# business_card_serial_uv.net
KiCad netlist of a schematic drawn in EAGLE
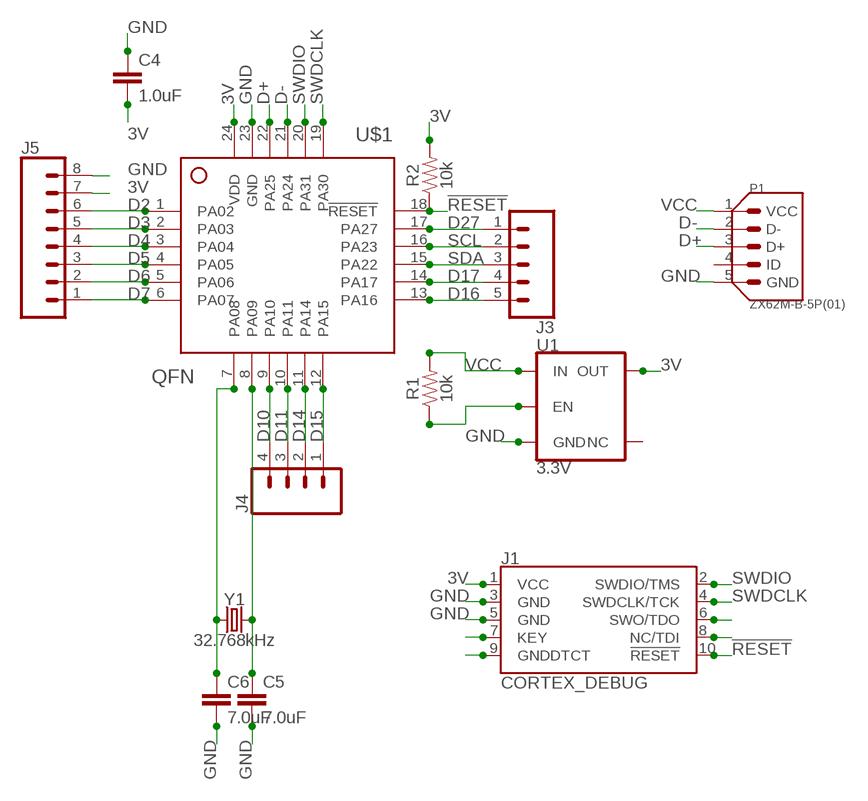
[diagram p0: schematic, sheet 1]

(export (version "E")
  (design (tool "Eeschema 10.0.6"))
  (components
    (comp (ref "C4")
      (value "1.0uF")
      (footprint "eagle-import:0402")
      (libsource (lib "eagle-import") (part "1.0UF-0402-16V-10%"))
    )
    (comp (ref "C5")
      (value "7.0uF")
      (footprint "eagle-import:0402")
      (libsource (lib "eagle-import") (part "1.0UF-0402-16V-10%"))
    )
    (comp (ref "C6")
      (value "7.0uF")
      (footprint "eagle-import:0402")
      (libsource (lib "eagle-import") (part "1.0UF-0402-16V-10%"))
    )
    (comp (ref "J1")
      (value "CORTEX_DEBUG")
      (footprint "eagle-import:2X5-PTH-1.27MM")
      (libsource (lib "eagle-import") (part "CORTEX_DEBUG_PTH"))
    )
    (comp (ref "J3")
      (value "CONN_05")
      (footprint "eagle-import:1X05")
      (libsource (lib "eagle-import") (part "CONN_05"))
    )
    (comp (ref "J4")
      (value "CONN_04")
      (footprint "eagle-import:1X04")
      (libsource (lib "eagle-import") (part "CONN_04"))
    )
    (comp (ref "J5")
      (value "CONN_08\"")
      (footprint "eagle-import:1X08")
      (libsource (lib "eagle-import") (part "CONN_08{dblquote}"))
    )
    (comp (ref "P1")
      (value "ZX62M-B-5P(01)")
      (footprint "eagle-import:HRS_ZX62M-B-5P(01)")
      (fields (field (name "MF") "Hirose") (field (name "MP") "ZX62M-B-5P_01_"))
      (libsource (lib "eagle-import") (part "ZX62M-B-5P(01)"))
    )
    (comp (ref "R1")
      (value "10k")
      (footprint "eagle-import:0603")
      (libsource (lib "eagle-import") (part "330OHM-0603-1/10W-1%"))
    )
    (comp (ref "R2")
      (value "10k")
      (footprint "eagle-import:0603")
      (libsource (lib "eagle-import") (part "330OHM-0603-1/10W-1%"))
    )
    (comp (ref "U$1")
      (value "QFN")
      (footprint "eagle-import:QFN24-4X4")
      (libsource (lib "eagle-import") (part "QFN"))
    )
    (comp (ref "U1")
      (value "3.3V")
      (footprint "eagle-import:SOT23-5")
      (libsource (lib "eagle-import") (part "V_REG_AP2112K-3.3V"))
    )
    (comp (ref "Y1")
      (value "32.768kHz")
      (footprint "eagle-import:CRYSTAL-SMD-3.2X1.5MM")
      (libsource (lib "eagle-import") (part "CRYSTAL-32.768KHZSMD-3.2X1.5"))
    )
  )
  (nets
    (net (code "1") (name "/3V") (class "Default")
      (node (ref "C4") (pin "2") (pinfunction "2_2") (pintype "passive"))
      (node (ref "J1") (pin "1") (pinfunction "VCC_1") (pintype "bidirectional"))
      (node (ref "J5") (pin "7") (pinfunction "7_7") (pintype "passive"))
      (node (ref "R2") (pin "2") (pinfunction "2_2") (pintype "passive"))
      (node (ref "U$1") (pin "24") (pinfunction "VDD_24") (pintype "bidirectional"))
      (node (ref "U1") (pin "5") (pinfunction "OUT_5") (pintype "passive"))
    )
    (net (code "2") (name "/D+") (class "Default")
      (node (ref "P1") (pin "3") (pinfunction "D+_3") (pintype "bidirectional"))
      (node (ref "U$1") (pin "22") (pinfunction "PA25_22") (pintype "bidirectional"))
    )
    (net (code "3") (name "/D-") (class "Default")
      (node (ref "P1") (pin "2") (pinfunction "D-_2") (pintype "bidirectional"))
      (node (ref "U$1") (pin "21") (pinfunction "PA24_21") (pintype "bidirectional"))
    )
    (net (code "4") (name "/D2") (class "Default")
      (node (ref "J5") (pin "6") (pinfunction "6_6") (pintype "passive"))
      (node (ref "U$1") (pin "1") (pinfunction "PA02_1") (pintype "bidirectional"))
    )
    (net (code "5") (name "/D3") (class "Default")
      (node (ref "J5") (pin "5") (pinfunction "5_5") (pintype "passive"))
      (node (ref "U$1") (pin "2") (pinfunction "PA03_2") (pintype "bidirectional"))
    )
    (net (code "6") (name "/D4") (class "Default")
      (node (ref "J5") (pin "4") (pinfunction "4_4") (pintype "passive"))
      (node (ref "U$1") (pin "3") (pinfunction "PA04_3") (pintype "bidirectional"))
    )
    (net (code "7") (name "/D5") (class "Default")
      (node (ref "J5") (pin "3") (pinfunction "3_3") (pintype "passive"))
      (node (ref "U$1") (pin "4") (pinfunction "PA05_4") (pintype "bidirectional"))
    )
    (net (code "8") (name "/D6") (class "Default")
      (node (ref "J5") (pin "2") (pinfunction "2_2") (pintype "passive"))
      (node (ref "U$1") (pin "5") (pinfunction "PA06_5") (pintype "bidirectional"))
    )
    (net (code "9") (name "/D7") (class "Default")
      (node (ref "J5") (pin "1") (pinfunction "1_1") (pintype "passive"))
      (node (ref "U$1") (pin "6") (pinfunction "PA07_6") (pintype "bidirectional"))
    )
    (net (code "10") (name "/D10") (class "Default")
      (node (ref "J4") (pin "4") (pinfunction "4_4") (pintype "passive"))
      (node (ref "U$1") (pin "9") (pinfunction "PA10_9") (pintype "bidirectional"))
    )
    (net (code "11") (name "/D11") (class "Default")
      (node (ref "J4") (pin "3") (pinfunction "3_3") (pintype "passive"))
      (node (ref "U$1") (pin "10") (pinfunction "PA11_10") (pintype "bidirectional"))
    )
    (net (code "12") (name "/D14") (class "Default")
      (node (ref "J4") (pin "2") (pinfunction "2_2") (pintype "passive"))
      (node (ref "U$1") (pin "11") (pinfunction "PA14_11") (pintype "bidirectional"))
    )
    (net (code "13") (name "/D15") (class "Default")
      (node (ref "J4") (pin "1") (pinfunction "1_1") (pintype "passive"))
      (node (ref "U$1") (pin "12") (pinfunction "PA15_12") (pintype "bidirectional"))
    )
    (net (code "14") (name "/D16") (class "Default")
      (node (ref "J3") (pin "5") (pinfunction "5_5") (pintype "passive"))
      (node (ref "U$1") (pin "13") (pinfunction "PA16_13") (pintype "bidirectional"))
    )
    (net (code "15") (name "/D17") (class "Default")
      (node (ref "J3") (pin "4") (pinfunction "4_4") (pintype "passive"))
      (node (ref "U$1") (pin "14") (pinfunction "PA17_14") (pintype "bidirectional"))
    )
    (net (code "16") (name "/D27") (class "Default")
      (node (ref "J3") (pin "1") (pinfunction "1_1") (pintype "passive"))
      (node (ref "U$1") (pin "17") (pinfunction "PA27_17") (pintype "bidirectional"))
    )
    (net (code "17") (name "/GND") (class "Default")
      (node (ref "C4") (pin "1") (pinfunction "1_1") (pintype "passive"))
      (node (ref "C5") (pin "2") (pinfunction "2_2") (pintype "passive"))
      (node (ref "C6") (pin "2") (pinfunction "2_2") (pintype "passive"))
      (node (ref "J1") (pin "3") (pinfunction "GND_3") (pintype "bidirectional"))
      (node (ref "J1") (pin "5") (pinfunction "GND_5") (pintype "bidirectional"))
      (node (ref "J5") (pin "8") (pinfunction "8_8") (pintype "passive"))
      (node (ref "P1") (pin "5") (pinfunction "GND_5") (pintype "passive"))
      (node (ref "U$1") (pin "23") (pinfunction "GND_23") (pintype "bidirectional"))
      (node (ref "U1") (pin "2") (pinfunction "GND_2") (pintype "input"))
    )
    (net (code "18") (name "/SCL") (class "Default")
      (node (ref "J3") (pin "2") (pinfunction "2_2") (pintype "passive"))
      (node (ref "U$1") (pin "16") (pinfunction "PA23_16") (pintype "bidirectional"))
    )
    (net (code "19") (name "/SDA") (class "Default")
      (node (ref "J3") (pin "3") (pinfunction "3_3") (pintype "passive"))
      (node (ref "U$1") (pin "15") (pinfunction "PA22_15") (pintype "bidirectional"))
    )
    (net (code "20") (name "/SWDCLK") (class "Default")
      (node (ref "J1") (pin "4") (pinfunction "SWDCLK/TCK_4") (pintype "bidirectional"))
      (node (ref "U$1") (pin "19") (pinfunction "PA30_19") (pintype "bidirectional"))
    )
    (net (code "21") (name "/SWDIO") (class "Default")
      (node (ref "J1") (pin "2") (pinfunction "SWDIO/TMS_2") (pintype "bidirectional"))
      (node (ref "U$1") (pin "20") (pinfunction "PA31_20") (pintype "bidirectional"))
    )
    (net (code "22") (name "/VCC") (class "Default")
      (node (ref "P1") (pin "1") (pinfunction "VCC_1") (pintype "power_in"))
      (node (ref "R1") (pin "2") (pinfunction "2_2") (pintype "passive"))
      (node (ref "U1") (pin "1") (pinfunction "IN_1") (pintype "input"))
    )
    (net (code "23") (name "/~{RESET}") (class "Default")
      (node (ref "J1") (pin "10") (pinfunction "~{RESET}_10") (pintype "bidirectional"))
      (node (ref "R2") (pin "1") (pinfunction "1_1") (pintype "passive"))
      (node (ref "U$1") (pin "18") (pinfunction "~{RESET}_18") (pintype "bidirectional"))
    )
    (net (code "24") (name "Net-(U$1-PA08)") (class "Default")
      (node (ref "C6") (pin "1") (pinfunction "1_1") (pintype "passive"))
      (node (ref "U$1") (pin "7") (pinfunction "PA08_7") (pintype "bidirectional"))
      (node (ref "Y1") (pin "P$1") (pinfunction "1_P$1") (pintype "passive"))
    )
    (net (code "25") (name "Net-(U$1-PA09)") (class "Default")
      (node (ref "C5") (pin "1") (pinfunction "1_1") (pintype "passive"))
      (node (ref "U$1") (pin "8") (pinfunction "PA09_8") (pintype "bidirectional"))
      (node (ref "Y1") (pin "P$2") (pinfunction "2_P$2") (pintype "passive"))
    )
    (net (code "26") (name "Net-(U1-EN)") (class "Default")
      (node (ref "R1") (pin "1") (pinfunction "1_1") (pintype "passive"))
      (node (ref "U1") (pin "3") (pinfunction "EN_3") (pintype "input"))
    )
    (net (code "27") (name "unconnected-(J1-GNDDTCT-Pad9)") (class "Default")
      (node (ref "J1") (pin "9") (pinfunction "GNDDTCT_9") (pintype "bidirectional"))
    )
    (net (code "28") (name "unconnected-(J1-KEY-Pad7)") (class "Default")
      (node (ref "J1") (pin "7") (pinfunction "KEY_7") (pintype "bidirectional"))
    )
    (net (code "29") (name "unconnected-(J1-NC{slash}TDI-Pad8)") (class "Default")
      (node (ref "J1") (pin "8") (pinfunction "NC/TDI_8") (pintype "bidirectional"))
    )
    (net (code "30") (name "unconnected-(J1-SWO{slash}TDO-Pad6)") (class "Default")
      (node (ref "J1") (pin "6") (pinfunction "SWO/TDO_6") (pintype "bidirectional"))
    )
    (net (code "31") (name "unconnected-(P1-ID-Pad4)") (class "Default")
      (node (ref "P1") (pin "4") (pinfunction "ID_4") (pintype "bidirectional"))
    )
    (net (code "32") (name "unconnected-(U1-NC-Pad4)") (class "Default")
      (node (ref "U1") (pin "4") (pinfunction "NC_4") (pintype "no_connect"))
    )
  )
)
